# Debug.net
KiCad netlist of a schematic drawn in Altium Designer
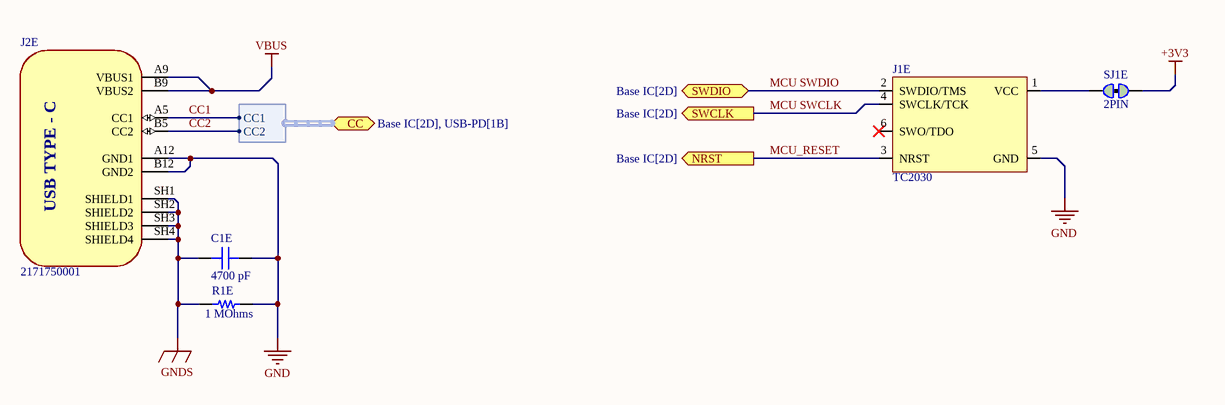
[diagram p0: Debug.SchDoc]

(export (version "E")
  (design (tool "Eeschema 10.0.6"))
  (components
    (comp (ref "C1E")
      (value "4700 pF")
      (footprint "CAP 0402_1005")
      (description "CAP CER 0402 4.7NF 16V X7R 10%")
      (fields (field (name "PART NUMBER") "C0402C472K4RECAUTO") (field (name "MANUFACTURER") "KEMET"))
      (libsource (lib "Postgres Altium Library - altium_library") (part "Capacitor"))
    )
    (comp (ref "J1E")
      (value "TC2030")
      (footprint "TC2030-FP")
      (description "Tag-Connect No-Solder SWD Debug Connector DO NOT PLACE")
      (fields (field (name "MANUFACTURER") "Tag-Connect"))
      (libsource (lib "Integrated_Library1") (part "TC2030"))
    )
    (comp (ref "J2E")
      (value "2171750001")
      (footprint "MOLEX_2171750001")
      (fields (field (name "MF") "Molex"))
      (libsource (lib "USB-C") (part "2171750001"))
    )
    (comp (ref "R1E")
      (value "1 MOhms")
      (footprint "RES 0402_1005")
      (description "RES SMD 1M OHM 1% 1/16W 0402")
      (fields (field (name "PART NUMBER") "AC0402FR-071ML") (field (name "TOLERANCE") "±1%"))
      (libsource (lib "Postgres Altium Library - altium_library") (part "Resistor"))
    )
    (comp (ref "SJ1E")
      (value "2PIN")
      (footprint "Rounded Jumper Joint")
      (libsource (lib "Jumper-SMD") (part "Rounded Jumper Joint"))
    )
  )
  (nets
    (net (code "2") (name "+3V3") (class "Default")
      (node (ref "SJ1E") (pin "2") (pinfunction "2_2") (pintype "passive"))
    )
    (net (code "3") (name "/CC1") (class "Default")
      (node (ref "J2E") (pin "A5") (pinfunction "CC1_A5") (pintype "bidirectional"))
    )
    (net (code "4") (name "/CC2") (class "Default")
      (node (ref "J2E") (pin "B5") (pinfunction "CC2_B5") (pintype "bidirectional"))
    )
    (net (code "5") (name "/MCU SWCLK") (class "Default")
      (node (ref "J1E") (pin "4") (pinfunction "SWCLK/TCK_4") (pintype "passive"))
    )
    (net (code "6") (name "/MCU SWDIO") (class "Default")
      (node (ref "J1E") (pin "2") (pinfunction "SWDIO/TMS_2") (pintype "passive"))
    )
    (net (code "7") (name "/MCU_RESET") (class "Default")
      (node (ref "J1E") (pin "3") (pinfunction "NRST_3") (pintype "passive"))
    )
    (net (code "10") (name "GND") (class "Default")
      (node (ref "C1E") (pin "2") (pinfunction "2_2") (pintype "passive"))
      (node (ref "J1E") (pin "5") (pinfunction "GND_5") (pintype "passive"))
      (node (ref "J2E") (pin "A12") (pinfunction "GND1_A12") (pintype "power_in"))
      (node (ref "J2E") (pin "B12") (pinfunction "GND2_B12") (pintype "power_in"))
      (node (ref "R1E") (pin "2") (pinfunction "2_2") (pintype "passive"))
    )
    (net (code "11") (name "GNDS") (class "Default")
      (node (ref "C1E") (pin "1") (pinfunction "1_1") (pintype "passive"))
      (node (ref "J2E") (pin "SH1") (pinfunction "SHIELD1_SH1") (pintype "passive"))
      (node (ref "J2E") (pin "SH2") (pinfunction "SHIELD2_SH2") (pintype "passive"))
      (node (ref "J2E") (pin "SH3") (pinfunction "SHIELD3_SH3") (pintype "passive"))
      (node (ref "J2E") (pin "SH4") (pinfunction "SHIELD4_SH4") (pintype "passive"))
      (node (ref "R1E") (pin "1") (pinfunction "1_1") (pintype "passive"))
    )
    (net (code "12") (name "Net-(J1E-VCC)") (class "Default")
      (node (ref "J1E") (pin "1") (pinfunction "VCC_1") (pintype "passive"))
      (node (ref "SJ1E") (pin "1") (pinfunction "1_1") (pintype "passive"))
    )
    (net (code "13") (name "VBUS") (class "Default")
      (node (ref "J2E") (pin "A9") (pinfunction "VBUS1_A9") (pintype "power_in"))
      (node (ref "J2E") (pin "B9") (pinfunction "VBUS2_B9") (pintype "power_in"))
    )
    (net (code "14") (name "unconnected-(J1E-SWO{slash}TDO-Pad6)") (class "Default")
      (node (ref "J1E") (pin "6") (pinfunction "SWO/TDO_6") (pintype "passive+no_connect"))
    )
  )
)
